# Ekspander.net
KiCad netlist of a schematic drawn in EAGLE
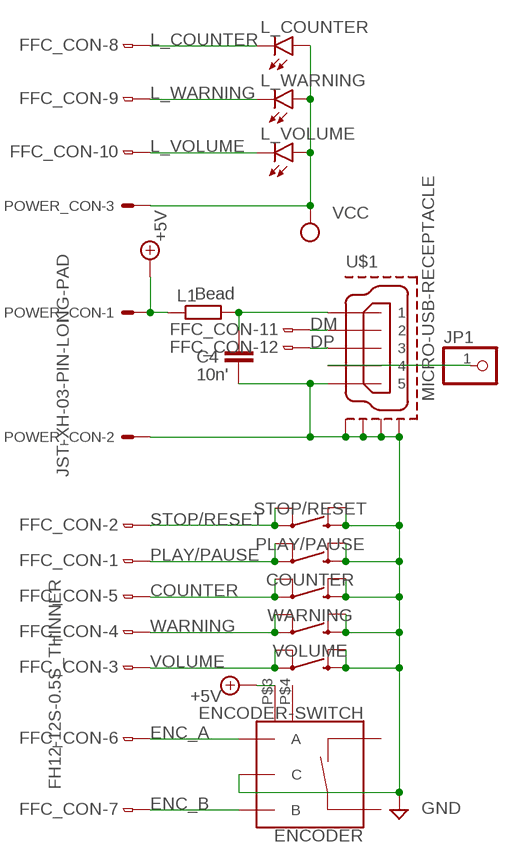
[diagram p0: schematic, sheet 1]

(export (version "E")
  (design (tool "Eeschema 10.0.6"))
  (components
    (comp (ref "C4")
      (value "10n'")
      (footprint "eagle-import:C0402")
      (libsource (lib "eagle-import") (part "C-EUC0402"))
    )
    (comp (ref "COUNTER")
      (value "MOMENTARY-SWITCH-SPST-PTH-12MM")
      (footprint "eagle-import:TACTILE_SWITCH_PTH_12MM")
      (libsource (lib "eagle-import") (part "MOMENTARY-SWITCH-SPST-PTH-12MM"))
    )
    (comp (ref "ENCODER")
      (value "ENCODER-SWITCH")
      (footprint "eagle-import:ROTARY_ENC_PLAIN")
      (libsource (lib "eagle-import") (part "ENCODER-SWITCH"))
    )
    (comp (ref "FFC_CON")
      (value "FH12-12S-0.5S_THINNER")
      (footprint "eagle-import:FH12-12S-0.5SH_THINER")
      (libsource (lib "eagle-import") (part "FH12-12S-0.5S_THINNER"))
    )
    (comp (ref "JP1")
      (value "PINHD-1X1")
      (footprint "eagle-import:1X01")
      (libsource (lib "eagle-import") (part "PINHD-1X1"))
    )
    (comp (ref "L1")
      (value "Bead")
      (footprint "eagle-import:R0603")
      (libsource (lib "eagle-import") (part "R-EU_R0603"))
    )
    (comp (ref "L_COUNTER")
      (value "LEDCHIPLED_0805")
      (footprint "eagle-import:CHIPLED_0805")
      (libsource (lib "eagle-import") (part "LEDCHIPLED_0805"))
    )
    (comp (ref "L_VOLUME")
      (value "LEDCHIPLED_0805")
      (footprint "eagle-import:CHIPLED_0805")
      (libsource (lib "eagle-import") (part "LEDCHIPLED_0805"))
    )
    (comp (ref "L_WARNING")
      (value "LEDCHIPLED_0805")
      (footprint "eagle-import:CHIPLED_0805")
      (libsource (lib "eagle-import") (part "LEDCHIPLED_0805"))
    )
    (comp (ref "PLAY/PAUSE")
      (value "MOMENTARY-SWITCH-SPST-PTH-12MM")
      (footprint "eagle-import:TACTILE_SWITCH_PTH_12MM")
      (libsource (lib "eagle-import") (part "MOMENTARY-SWITCH-SPST-PTH-12MM"))
    )
    (comp (ref "POWER_CON")
      (value "JST-XH-03-PIN-LONG-PAD")
      (footprint "eagle-import:JST-XH-03-PACKAGE-LONG-PAD")
      (libsource (lib "eagle-import") (part "JST-XH-03-PIN-LONG-PAD"))
    )
    (comp (ref "STOP/RESET")
      (value "MOMENTARY-SWITCH-SPST-PTH-12MM")
      (footprint "eagle-import:TACTILE_SWITCH_PTH_12MM")
      (libsource (lib "eagle-import") (part "MOMENTARY-SWITCH-SPST-PTH-12MM"))
    )
    (comp (ref "U$1")
      (value "MICRO-USB-RECEPTACLE")
      (footprint "eagle-import:47589-0002")
      (libsource (lib "eagle-import") (part "MICRO-USB-RECEPTACLE"))
    )
    (comp (ref "VOLUME")
      (value "MOMENTARY-SWITCH-SPST-PTH-12MM")
      (footprint "eagle-import:TACTILE_SWITCH_PTH_12MM")
      (libsource (lib "eagle-import") (part "MOMENTARY-SWITCH-SPST-PTH-12MM"))
    )
    (comp (ref "WARNING")
      (value "MOMENTARY-SWITCH-SPST-PTH-12MM")
      (footprint "eagle-import:TACTILE_SWITCH_PTH_12MM")
      (libsource (lib "eagle-import") (part "MOMENTARY-SWITCH-SPST-PTH-12MM"))
    )
  )
  (nets
    (net (code "1") (name "+5V") (class "Default")
      (node (ref "ENCODER") (pin "P$3") (pinfunction "GND1_P$3") (pintype "bidirectional"))
      (node (ref "L1") (pin "1") (pinfunction "1_1") (pintype "passive"))
      (node (ref "POWER_CON") (pin "1") (pinfunction "S_1") (pintype "passive"))
    )
    (net (code "2") (name "/COUNTER") (class "Default")
      (node (ref "COUNTER") (pin "1") (pinfunction "1_1") (pintype "passive"))
      (node (ref "COUNTER") (pin "2") (pinfunction "3_2") (pintype "passive"))
      (node (ref "FFC_CON") (pin "5") (pinfunction "1_5") (pintype "passive"))
    )
    (net (code "3") (name "/DM") (class "Default")
      (node (ref "FFC_CON") (pin "11") (pinfunction "1_11") (pintype "passive"))
      (node (ref "U$1") (pin "2") (pinfunction "2_2") (pintype "input"))
    )
    (net (code "4") (name "/DP") (class "Default")
      (node (ref "FFC_CON") (pin "12") (pinfunction "1_12") (pintype "passive"))
      (node (ref "U$1") (pin "3") (pinfunction "3_3") (pintype "input"))
    )
    (net (code "5") (name "/ENC_A") (class "Default")
      (node (ref "ENCODER") (pin "A") (pinfunction "A_A") (pintype "bidirectional"))
      (node (ref "FFC_CON") (pin "6") (pinfunction "1_6") (pintype "passive"))
    )
    (net (code "6") (name "/ENC_B") (class "Default")
      (node (ref "ENCODER") (pin "B") (pinfunction "B_B") (pintype "bidirectional"))
      (node (ref "FFC_CON") (pin "7") (pinfunction "1_7") (pintype "passive"))
    )
    (net (code "7") (name "/L_COUNTER") (class "Default")
      (node (ref "FFC_CON") (pin "8") (pinfunction "1_8") (pintype "passive"))
      (node (ref "L_COUNTER") (pin "C") (pinfunction "C_C") (pintype "passive"))
    )
    (net (code "8") (name "/L_VOLUME") (class "Default")
      (node (ref "FFC_CON") (pin "10") (pinfunction "1_10") (pintype "passive"))
      (node (ref "L_VOLUME") (pin "C") (pinfunction "C_C") (pintype "passive"))
    )
    (net (code "9") (name "/L_WARNING") (class "Default")
      (node (ref "FFC_CON") (pin "9") (pinfunction "1_9") (pintype "passive"))
      (node (ref "L_WARNING") (pin "C") (pinfunction "C_C") (pintype "passive"))
    )
    (net (code "10") (name "/PLAY{slash}PAUSE") (class "Default")
      (node (ref "FFC_CON") (pin "1") (pinfunction "1_1") (pintype "passive"))
      (node (ref "PLAY/PAUSE") (pin "1") (pinfunction "1_1") (pintype "passive"))
      (node (ref "PLAY/PAUSE") (pin "2") (pinfunction "3_2") (pintype "passive"))
    )
    (net (code "11") (name "/STOP{slash}RESET") (class "Default")
      (node (ref "FFC_CON") (pin "2") (pinfunction "1_2") (pintype "passive"))
      (node (ref "STOP/RESET") (pin "1") (pinfunction "1_1") (pintype "passive"))
      (node (ref "STOP/RESET") (pin "2") (pinfunction "3_2") (pintype "passive"))
    )
    (net (code "12") (name "/VOLUME") (class "Default")
      (node (ref "FFC_CON") (pin "3") (pinfunction "1_3") (pintype "passive"))
      (node (ref "VOLUME") (pin "1") (pinfunction "1_1") (pintype "passive"))
      (node (ref "VOLUME") (pin "2") (pinfunction "3_2") (pintype "passive"))
    )
    (net (code "13") (name "/WARNING") (class "Default")
      (node (ref "FFC_CON") (pin "4") (pinfunction "1_4") (pintype "passive"))
      (node (ref "WARNING") (pin "1") (pinfunction "1_1") (pintype "passive"))
      (node (ref "WARNING") (pin "2") (pinfunction "3_2") (pintype "passive"))
    )
    (net (code "14") (name "GND") (class "Default")
      (node (ref "C4") (pin "2") (pinfunction "2_2") (pintype "passive"))
      (node (ref "COUNTER") (pin "3") (pinfunction "2_3") (pintype "passive"))
      (node (ref "COUNTER") (pin "4") (pinfunction "4_4") (pintype "passive"))
      (node (ref "ENCODER") (pin "C") (pinfunction "C_C") (pintype "bidirectional"))
      (node (ref "PLAY/PAUSE") (pin "3") (pinfunction "2_3") (pintype "passive"))
      (node (ref "PLAY/PAUSE") (pin "4") (pinfunction "4_4") (pintype "passive"))
      (node (ref "POWER_CON") (pin "2") (pinfunction "S_2") (pintype "passive"))
      (node (ref "STOP/RESET") (pin "3") (pinfunction "2_3") (pintype "passive"))
      (node (ref "STOP/RESET") (pin "4") (pinfunction "4_4") (pintype "passive"))
      (node (ref "U$1") (pin "5") (pinfunction "5_5") (pintype "input"))
      (node (ref "U$1") (pin "CASING1") (pinfunction "GND1_CASING1") (pintype "bidirectional"))
      (node (ref "U$1") (pin "CASING2") (pinfunction "GND2_CASING2") (pintype "bidirectional"))
      (node (ref "U$1") (pin "CASING3") (pinfunction "GND3_CASING3") (pintype "bidirectional"))
      (node (ref "U$1") (pin "CASING4") (pinfunction "GND4_CASING4") (pintype "bidirectional"))
      (node (ref "VOLUME") (pin "3") (pinfunction "2_3") (pintype "passive"))
      (node (ref "VOLUME") (pin "4") (pinfunction "4_4") (pintype "passive"))
      (node (ref "WARNING") (pin "3") (pinfunction "2_3") (pintype "passive"))
      (node (ref "WARNING") (pin "4") (pinfunction "4_4") (pintype "passive"))
    )
    (net (code "15") (name "Net-(C4-Pad1)") (class "Default")
      (node (ref "C4") (pin "1") (pinfunction "1_1") (pintype "passive"))
      (node (ref "L1") (pin "2") (pinfunction "2_2") (pintype "passive"))
      (node (ref "U$1") (pin "1") (pinfunction "1_1") (pintype "input"))
    )
    (net (code "16") (name "Net-(JP1-Pad1)") (class "Default")
      (node (ref "JP1") (pin "1") (pinfunction "1_1") (pintype "passive"))
      (node (ref "U$1") (pin "4") (pinfunction "4_4") (pintype "input"))
    )
    (net (code "17") (name "VCC") (class "Default")
      (node (ref "L_COUNTER") (pin "A") (pinfunction "A_A") (pintype "passive"))
      (node (ref "L_VOLUME") (pin "A") (pinfunction "A_A") (pintype "passive"))
      (node (ref "L_WARNING") (pin "A") (pinfunction "A_A") (pintype "passive"))
      (node (ref "POWER_CON") (pin "3") (pinfunction "S_3") (pintype "passive"))
    )
    (net (code "18") (name "unconnected-(ENCODER-GND2-PadP$4)") (class "Default")
      (node (ref "ENCODER") (pin "P$4") (pinfunction "GND2_P$4") (pintype "bidirectional"))
    )
    (net (code "19") (name "unconnected-(ENCODER-PadSW+)") (class "Default")
      (node (ref "ENCODER") (pin "SW+") (pinfunction "SW+_SW+") (pintype "bidirectional"))
    )
    (net (code "20") (name "unconnected-(ENCODER-PadSW-)") (class "Default")
      (node (ref "ENCODER") (pin "SW-") (pinfunction "SW-_SW-") (pintype "bidirectional"))
    )
  )
)
